# UltrasonicSensor.net
KiCad netlist of a schematic drawn in EAGLE
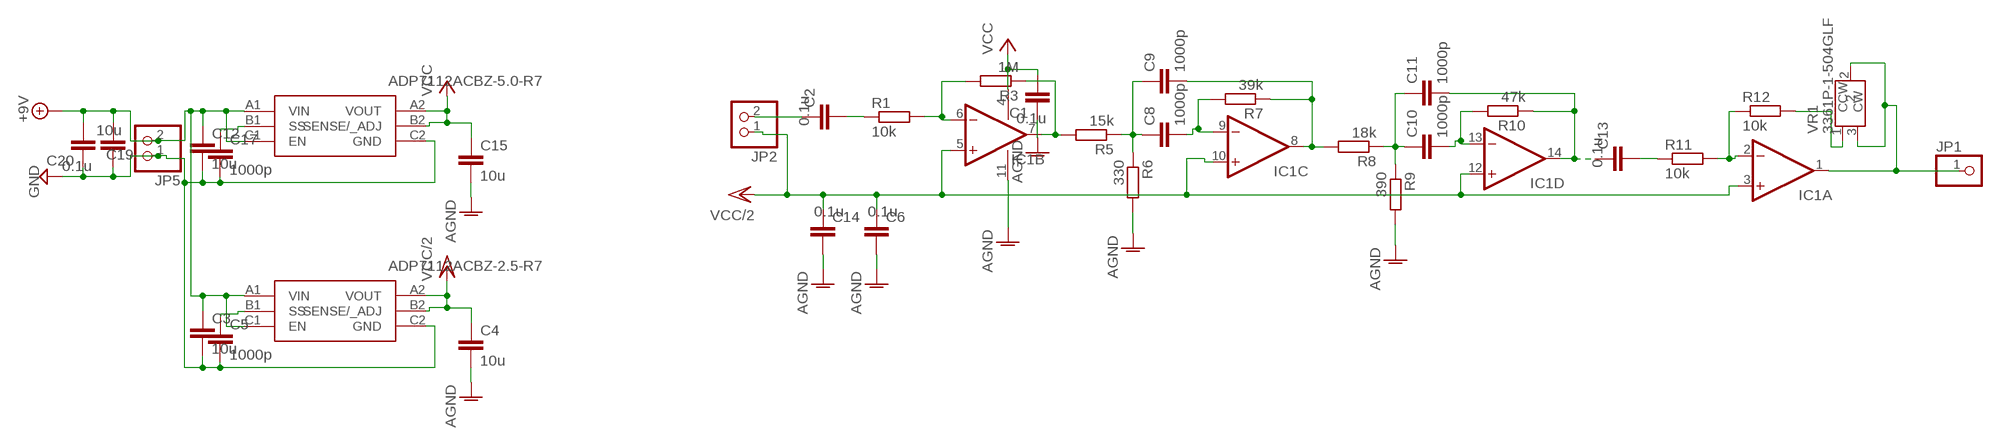
[diagram p0: schematic, sheet 1]

(export (version "E")
  (design (tool "Eeschema 10.0.6"))
  (components
    (comp (ref "C1")
      (value "0.1u")
      (footprint "eagle-import:C1608")
      (libsource (lib "eagle-import") (part "C-EUC1608"))
    )
    (comp (ref "C2")
      (value "0.1u")
      (footprint "eagle-import:C1608")
      (libsource (lib "eagle-import") (part "C-EUC1608"))
    )
    (comp (ref "C3")
      (value "10u")
      (footprint "eagle-import:C2012")
      (libsource (lib "eagle-import") (part "C-EUC2012"))
    )
    (comp (ref "C4")
      (value "10u")
      (footprint "eagle-import:C2012")
      (libsource (lib "eagle-import") (part "C-EUC2012"))
    )
    (comp (ref "C5")
      (value "1000p")
      (footprint "eagle-import:C1608")
      (libsource (lib "eagle-import") (part "C-EUC1608"))
    )
    (comp (ref "C6")
      (value "0.1u")
      (footprint "eagle-import:C1608")
      (libsource (lib "eagle-import") (part "C-EUC1608"))
    )
    (comp (ref "C8")
      (value "1000p")
      (footprint "eagle-import:C1608")
      (libsource (lib "eagle-import") (part "C-EUC1608"))
    )
    (comp (ref "C9")
      (value "1000p")
      (footprint "eagle-import:C1608")
      (libsource (lib "eagle-import") (part "C-EUC1608"))
    )
    (comp (ref "C10")
      (value "1000p")
      (footprint "eagle-import:C1608")
      (libsource (lib "eagle-import") (part "C-EUC1608"))
    )
    (comp (ref "C11")
      (value "1000p")
      (footprint "eagle-import:C1608")
      (libsource (lib "eagle-import") (part "C-EUC1608"))
    )
    (comp (ref "C12")
      (value "10u")
      (footprint "eagle-import:C2012")
      (libsource (lib "eagle-import") (part "C-EUC2012"))
    )
    (comp (ref "C13")
      (value "0.1u")
      (footprint "eagle-import:C1608")
      (libsource (lib "eagle-import") (part "C-EUC1608"))
    )
    (comp (ref "C14")
      (value "0.1u")
      (footprint "eagle-import:C1608")
      (libsource (lib "eagle-import") (part "C-EUC1608"))
    )
    (comp (ref "C15")
      (value "10u")
      (footprint "eagle-import:C2012")
      (libsource (lib "eagle-import") (part "C-EUC2012"))
    )
    (comp (ref "C17")
      (value "1000p")
      (footprint "eagle-import:C1608")
      (libsource (lib "eagle-import") (part "C-EUC1608"))
    )
    (comp (ref "C19")
      (value "10u")
      (footprint "eagle-import:C2012")
      (libsource (lib "eagle-import") (part "C-EUC2012"))
    )
    (comp (ref "C20")
      (value "0.1u")
      (footprint "eagle-import:C1608")
      (libsource (lib "eagle-import") (part "C-EUC1608"))
    )
    (comp (ref "IC1")
      (value "NJM2734M")
      (footprint "eagle-import:NJM2734M")
      (libsource (lib "eagle-import") (part "NJM2734M"))
    )
    (comp (ref "JP1")
      (value "PINHD-1X1")
      (footprint "eagle-import:1X01")
      (libsource (lib "eagle-import") (part "PINHD-1X1"))
    )
    (comp (ref "JP2")
      (value "PINHD-1X2")
      (footprint "eagle-import:1X02")
      (libsource (lib "eagle-import") (part "PINHD-1X2"))
    )
    (comp (ref "JP5")
      (value "PINHD-1X2")
      (footprint "eagle-import:1X02")
      (libsource (lib "eagle-import") (part "PINHD-1X2"))
    )
    (comp (ref "PS1")
      (value "ADP7112ACBZ-2.5-R7")
      (footprint "eagle-import:BGA6C40P2X3_95X116X56")
      (fields
        (field (name "ARROW_PART_NUMBER") "ADP7112ACBZ-3.3-R7")
        (field (name "MOUSER_PART_NUMBER") "584-ADP7112ACBZ3.3R7")
      )
      (libsource (lib "eagle-import") (part "ADP7112ACBZ-3.3-R7"))
    )
    (comp (ref "PS2")
      (value "ADP7112ACBZ-5.0-R7")
      (footprint "eagle-import:BGA6C40P2X3_95X116X56")
      (fields
        (field (name "ARROW_PART_NUMBER") "ADP7112ACBZ-3.3-R7")
        (field (name "MOUSER_PART_NUMBER") "584-ADP7112ACBZ3.3R7")
      )
      (libsource (lib "eagle-import") (part "ADP7112ACBZ-3.3-R7"))
    )
    (comp (ref "R1")
      (value "10k")
      (footprint "eagle-import:R0603")
      (libsource (lib "eagle-import") (part "R-EU_R0603"))
    )
    (comp (ref "R3")
      (value "1M")
      (footprint "eagle-import:R0603")
      (libsource (lib "eagle-import") (part "R-EU_R0603"))
    )
    (comp (ref "R5")
      (value "15k")
      (footprint "eagle-import:R0603")
      (libsource (lib "eagle-import") (part "R-EU_R0603"))
    )
    (comp (ref "R6")
      (value "330")
      (footprint "eagle-import:R0603")
      (libsource (lib "eagle-import") (part "R-EU_R0603"))
    )
    (comp (ref "R7")
      (value "39k")
      (footprint "eagle-import:R0603")
      (libsource (lib "eagle-import") (part "R-EU_R0603"))
    )
    (comp (ref "R8")
      (value "18k")
      (footprint "eagle-import:R0603")
      (libsource (lib "eagle-import") (part "R-EU_R0603"))
    )
    (comp (ref "R9")
      (value "390")
      (footprint "eagle-import:R0603")
      (libsource (lib "eagle-import") (part "R-EU_R0603"))
    )
    (comp (ref "R10")
      (value "47k")
      (footprint "eagle-import:R0603")
      (libsource (lib "eagle-import") (part "R-EU_R0603"))
    )
    (comp (ref "R11")
      (value "10k")
      (footprint "eagle-import:R0603")
      (libsource (lib "eagle-import") (part "R-EU_R0603"))
    )
    (comp (ref "R12")
      (value "10k")
      (footprint "eagle-import:R0603")
      (libsource (lib "eagle-import") (part "R-EU_R0603"))
    )
    (comp (ref "VR1")
      (value "3361P-1-504GLF")
      (footprint "eagle-import:3361P1253GLF")
      (fields (field (name "MOUSER_PART_NUMBER") "652-3361P-1-504GLF"))
      (libsource (lib "eagle-import") (part "3361P-1-504GLF"))
    )
  )
  (nets
    (net (code "1") (name "+9V") (class "Default")
      (node (ref "C12") (pin "1") (pinfunction "1_1") (pintype "passive"))
      (node (ref "C19") (pin "2") (pinfunction "2_2") (pintype "passive"))
      (node (ref "C20") (pin "2") (pinfunction "2_2") (pintype "passive"))
      (node (ref "C3") (pin "1") (pinfunction "1_1") (pintype "passive"))
      (node (ref "JP5") (pin "2") (pinfunction "2_2") (pintype "passive"))
      (node (ref "PS1") (pin "A1") (pinfunction "VIN_A1") (pintype "bidirectional"))
      (node (ref "PS1") (pin "C1") (pinfunction "EN_C1") (pintype "bidirectional"))
      (node (ref "PS2") (pin "A1") (pinfunction "VIN_A1") (pintype "bidirectional"))
      (node (ref "PS2") (pin "C1") (pinfunction "EN_C1") (pintype "bidirectional"))
    )
    (net (code "2") (name "AGND") (class "Default")
      (node (ref "C1") (pin "1") (pinfunction "1_1") (pintype "passive"))
      (node (ref "C14") (pin "2") (pinfunction "2_2") (pintype "passive"))
      (node (ref "C15") (pin "2") (pinfunction "2_2") (pintype "passive"))
      (node (ref "C4") (pin "2") (pinfunction "2_2") (pintype "passive"))
      (node (ref "C6") (pin "2") (pinfunction "2_2") (pintype "passive"))
      (node (ref "IC1") (pin "11") (pinfunction "V-_11") (pintype "power_in"))
      (node (ref "R6") (pin "2") (pinfunction "2_2") (pintype "passive"))
      (node (ref "R9") (pin "2") (pinfunction "2_2") (pintype "passive"))
    )
    (net (code "3") (name "GND") (class "Default")
      (node (ref "C12") (pin "2") (pinfunction "2_2") (pintype "passive"))
      (node (ref "C17") (pin "2") (pinfunction "2_2") (pintype "passive"))
      (node (ref "C19") (pin "1") (pinfunction "1_1") (pintype "passive"))
      (node (ref "C20") (pin "1") (pinfunction "1_1") (pintype "passive"))
      (node (ref "C3") (pin "2") (pinfunction "2_2") (pintype "passive"))
      (node (ref "C5") (pin "2") (pinfunction "2_2") (pintype "passive"))
      (node (ref "JP5") (pin "1") (pinfunction "1_1") (pintype "passive"))
      (node (ref "PS1") (pin "C2") (pinfunction "GND_C2") (pintype "bidirectional"))
      (node (ref "PS2") (pin "C2") (pinfunction "GND_C2") (pintype "bidirectional"))
    )
    (net (code "4") (name "Net-(C2-Pad1)") (class "Default")
      (node (ref "C2") (pin "1") (pinfunction "1_1") (pintype "passive"))
      (node (ref "JP2") (pin "2") (pinfunction "2_2") (pintype "passive"))
    )
    (net (code "5") (name "Net-(C2-Pad2)") (class "Default")
      (node (ref "C2") (pin "2") (pinfunction "2_2") (pintype "passive"))
      (node (ref "R1") (pin "1") (pinfunction "1_1") (pintype "passive"))
    )
    (net (code "6") (name "Net-(C8-Pad1)") (class "Default")
      (node (ref "C8") (pin "1") (pinfunction "1_1") (pintype "passive"))
      (node (ref "C9") (pin "1") (pinfunction "1_1") (pintype "passive"))
      (node (ref "R5") (pin "1") (pinfunction "1_1") (pintype "passive"))
      (node (ref "R6") (pin "1") (pinfunction "1_1") (pintype "passive"))
    )
    (net (code "7") (name "Net-(C10-Pad1)") (class "Default")
      (node (ref "C10") (pin "1") (pinfunction "1_1") (pintype "passive"))
      (node (ref "C11") (pin "1") (pinfunction "1_1") (pintype "passive"))
      (node (ref "R8") (pin "1") (pinfunction "1_1") (pintype "passive"))
      (node (ref "R9") (pin "1") (pinfunction "1_1") (pintype "passive"))
    )
    (net (code "8") (name "Net-(C13-Pad2)") (class "Default")
      (node (ref "C13") (pin "2") (pinfunction "2_2") (pintype "passive"))
      (node (ref "R11") (pin "1") (pinfunction "1_1") (pintype "passive"))
    )
    (net (code "9") (name "Net-(IC1A--IN)") (class "Default")
      (node (ref "IC1") (pin "2") (pinfunction "-IN_2") (pintype "input"))
      (node (ref "R11") (pin "2") (pinfunction "2_2") (pintype "passive"))
      (node (ref "R12") (pin "1") (pinfunction "1_1") (pintype "passive"))
    )
    (net (code "10") (name "Net-(IC1A-OUT)") (class "Default")
      (node (ref "IC1") (pin "1") (pinfunction "OUT_1") (pintype "output"))
      (node (ref "JP1") (pin "1") (pinfunction "1_1") (pintype "passive"))
      (node (ref "VR1") (pin "2") (pinfunction "2_2") (pintype "bidirectional"))
      (node (ref "VR1") (pin "3") (pinfunction "CW_3") (pintype "bidirectional"))
    )
    (net (code "11") (name "Net-(IC1B--IN)") (class "Default")
      (node (ref "IC1") (pin "6") (pinfunction "-IN_6") (pintype "input"))
      (node (ref "R1") (pin "2") (pinfunction "2_2") (pintype "passive"))
      (node (ref "R3") (pin "2") (pinfunction "2_2") (pintype "passive"))
    )
    (net (code "12") (name "Net-(IC1B-OUT)") (class "Default")
      (node (ref "IC1") (pin "7") (pinfunction "OUT_7") (pintype "output"))
      (node (ref "R3") (pin "1") (pinfunction "1_1") (pintype "passive"))
      (node (ref "R5") (pin "2") (pinfunction "2_2") (pintype "passive"))
    )
    (net (code "13") (name "Net-(IC1C--IN)") (class "Default")
      (node (ref "C8") (pin "2") (pinfunction "2_2") (pintype "passive"))
      (node (ref "IC1") (pin "9") (pinfunction "-IN_9") (pintype "input"))
      (node (ref "R7") (pin "2") (pinfunction "2_2") (pintype "passive"))
    )
    (net (code "14") (name "Net-(IC1C-OUT)") (class "Default")
      (node (ref "C9") (pin "2") (pinfunction "2_2") (pintype "passive"))
      (node (ref "IC1") (pin "8") (pinfunction "OUT_8") (pintype "output"))
      (node (ref "R7") (pin "1") (pinfunction "1_1") (pintype "passive"))
      (node (ref "R8") (pin "2") (pinfunction "2_2") (pintype "passive"))
    )
    (net (code "15") (name "Net-(IC1D--IN)") (class "Default")
      (node (ref "C10") (pin "2") (pinfunction "2_2") (pintype "passive"))
      (node (ref "IC1") (pin "13") (pinfunction "-IN_13") (pintype "input"))
      (node (ref "R10") (pin "2") (pinfunction "2_2") (pintype "passive"))
    )
    (net (code "16") (name "Net-(IC1D-OUT)") (class "Default")
      (node (ref "C11") (pin "2") (pinfunction "2_2") (pintype "passive"))
      (node (ref "C13") (pin "1") (pinfunction "1_1") (pintype "passive"))
      (node (ref "IC1") (pin "14") (pinfunction "OUT_14") (pintype "output"))
      (node (ref "R10") (pin "1") (pinfunction "1_1") (pintype "passive"))
    )
    (net (code "17") (name "Net-(PS1-SS)") (class "Default")
      (node (ref "C5") (pin "1") (pinfunction "1_1") (pintype "passive"))
      (node (ref "PS1") (pin "B1") (pinfunction "SS_B1") (pintype "bidirectional"))
    )
    (net (code "18") (name "Net-(PS2-SS)") (class "Default")
      (node (ref "C17") (pin "1") (pinfunction "1_1") (pintype "passive"))
      (node (ref "PS2") (pin "B1") (pinfunction "SS_B1") (pintype "bidirectional"))
    )
    (net (code "19") (name "Net-(VR1-CCW)") (class "Default")
      (node (ref "R12") (pin "2") (pinfunction "2_2") (pintype "passive"))
      (node (ref "VR1") (pin "1") (pinfunction "CCW_1") (pintype "bidirectional"))
    )
    (net (code "20") (name "VCC") (class "Default")
      (node (ref "C1") (pin "2") (pinfunction "2_2") (pintype "passive"))
      (node (ref "C15") (pin "1") (pinfunction "1_1") (pintype "passive"))
      (node (ref "IC1") (pin "4") (pinfunction "V+_4") (pintype "power_in"))
      (node (ref "PS2") (pin "A2") (pinfunction "VOUT_A2") (pintype "bidirectional"))
      (node (ref "PS2") (pin "B2") (pinfunction "SENSE/_ADJ_B2") (pintype "bidirectional"))
    )
    (net (code "21") (name "VCC{slash}2") (class "Default")
      (node (ref "C14") (pin "1") (pinfunction "1_1") (pintype "passive"))
      (node (ref "C4") (pin "1") (pinfunction "1_1") (pintype "passive"))
      (node (ref "C6") (pin "1") (pinfunction "1_1") (pintype "passive"))
      (node (ref "IC1") (pin "10") (pinfunction "+IN_10") (pintype "input"))
      (node (ref "IC1") (pin "12") (pinfunction "+IN_12") (pintype "input"))
      (node (ref "IC1") (pin "3") (pinfunction "+IN_3") (pintype "input"))
      (node (ref "IC1") (pin "5") (pinfunction "+IN_5") (pintype "input"))
      (node (ref "JP2") (pin "1") (pinfunction "1_1") (pintype "passive"))
      (node (ref "PS1") (pin "A2") (pinfunction "VOUT_A2") (pintype "bidirectional"))
      (node (ref "PS1") (pin "B2") (pinfunction "SENSE/_ADJ_B2") (pintype "bidirectional"))
    )
  )
)
